# RefOsc10MHz_2V1.net
KiCad netlist of a schematic drawn in EAGLE
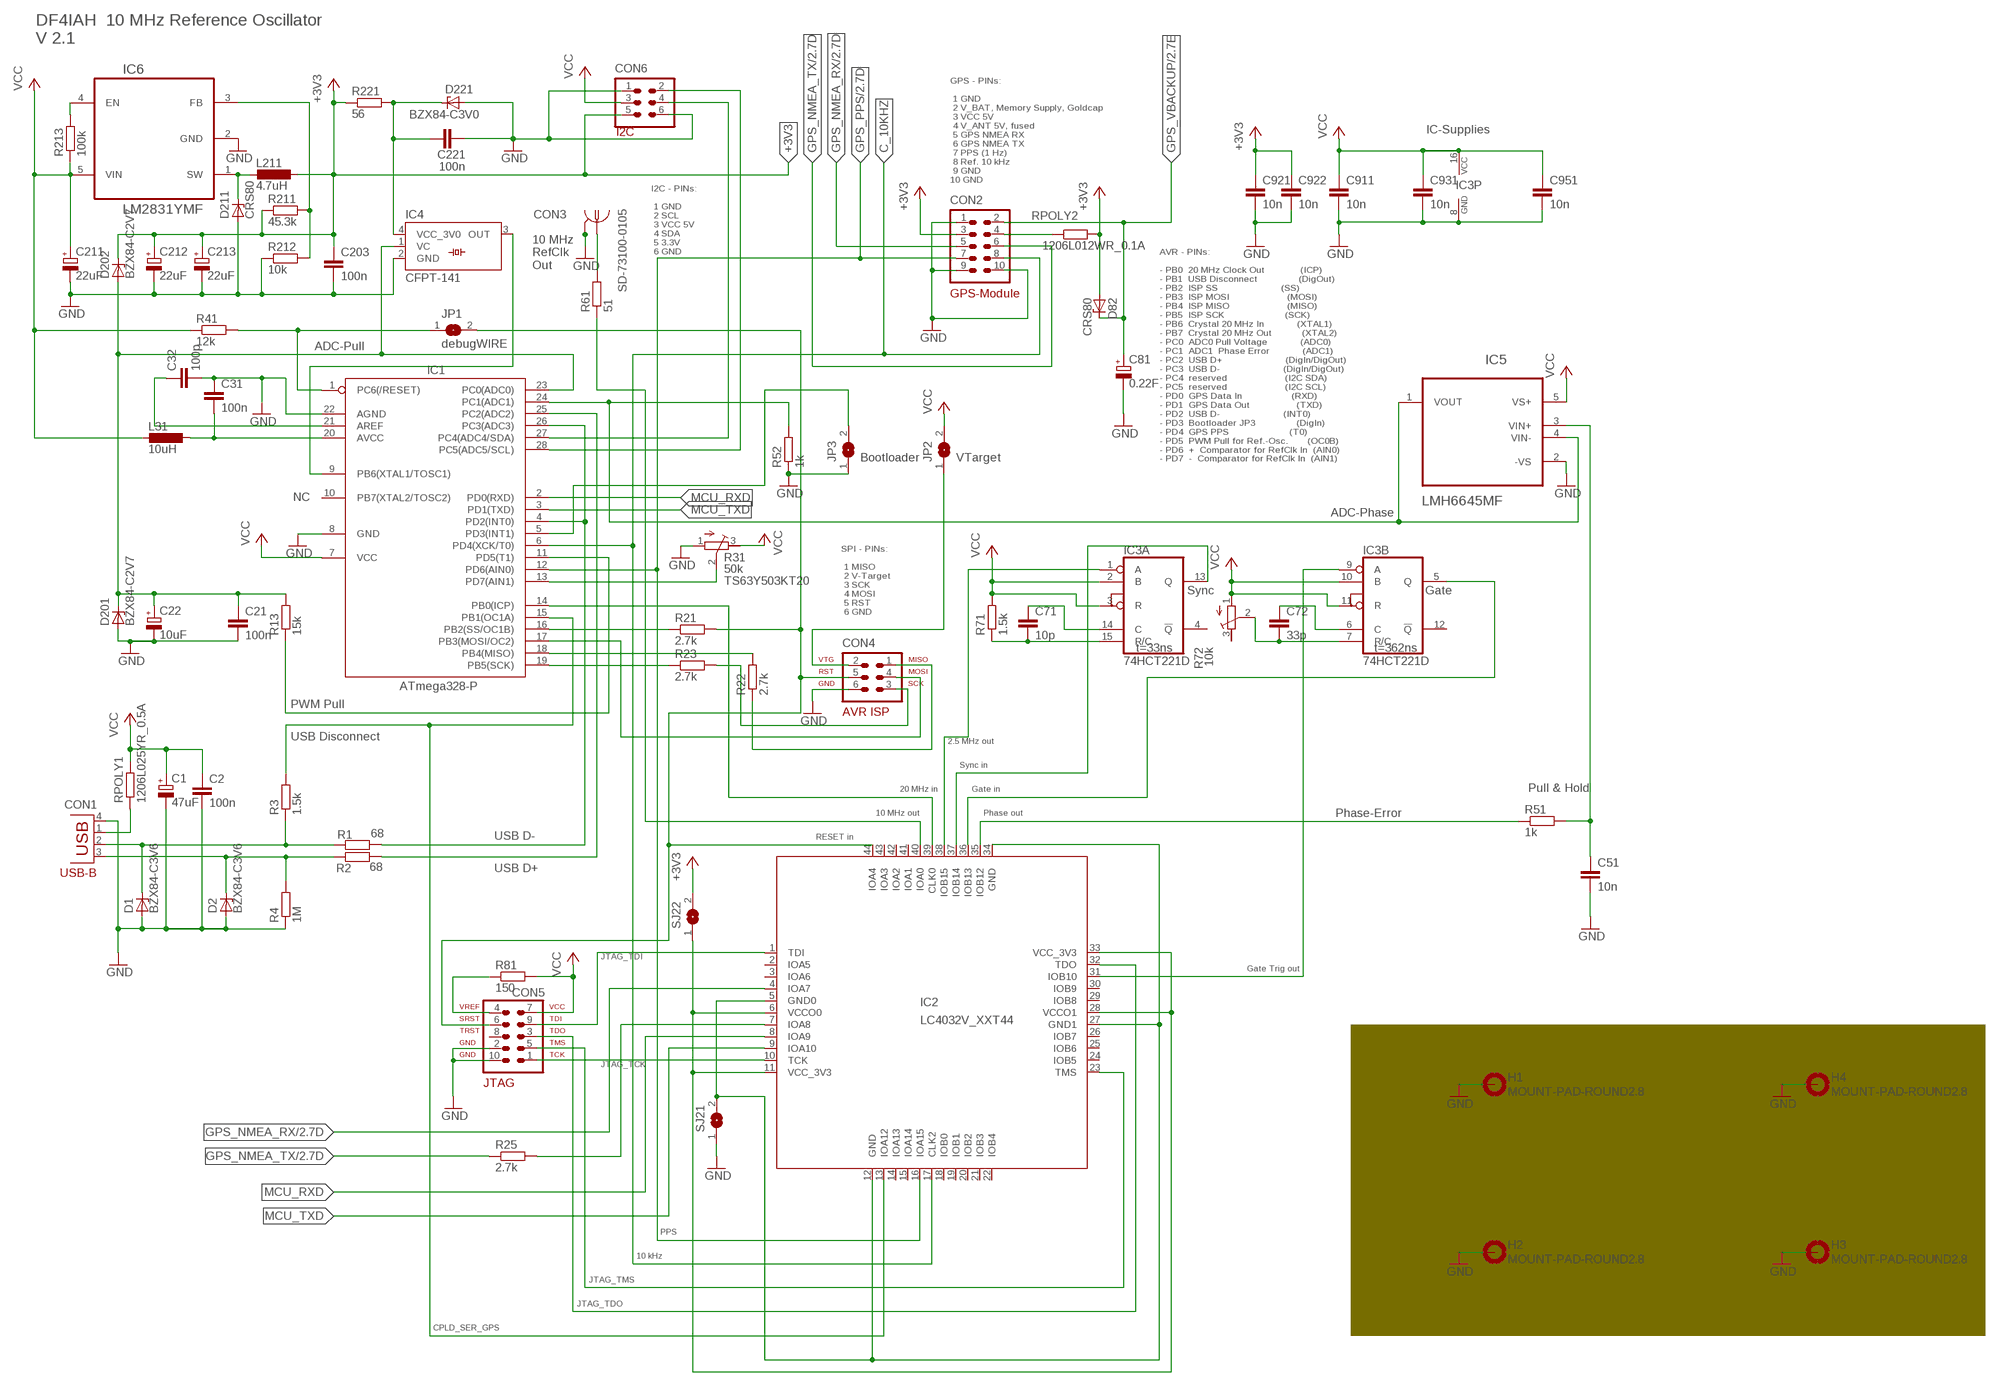
[diagram p0: schematic, sheet 1]
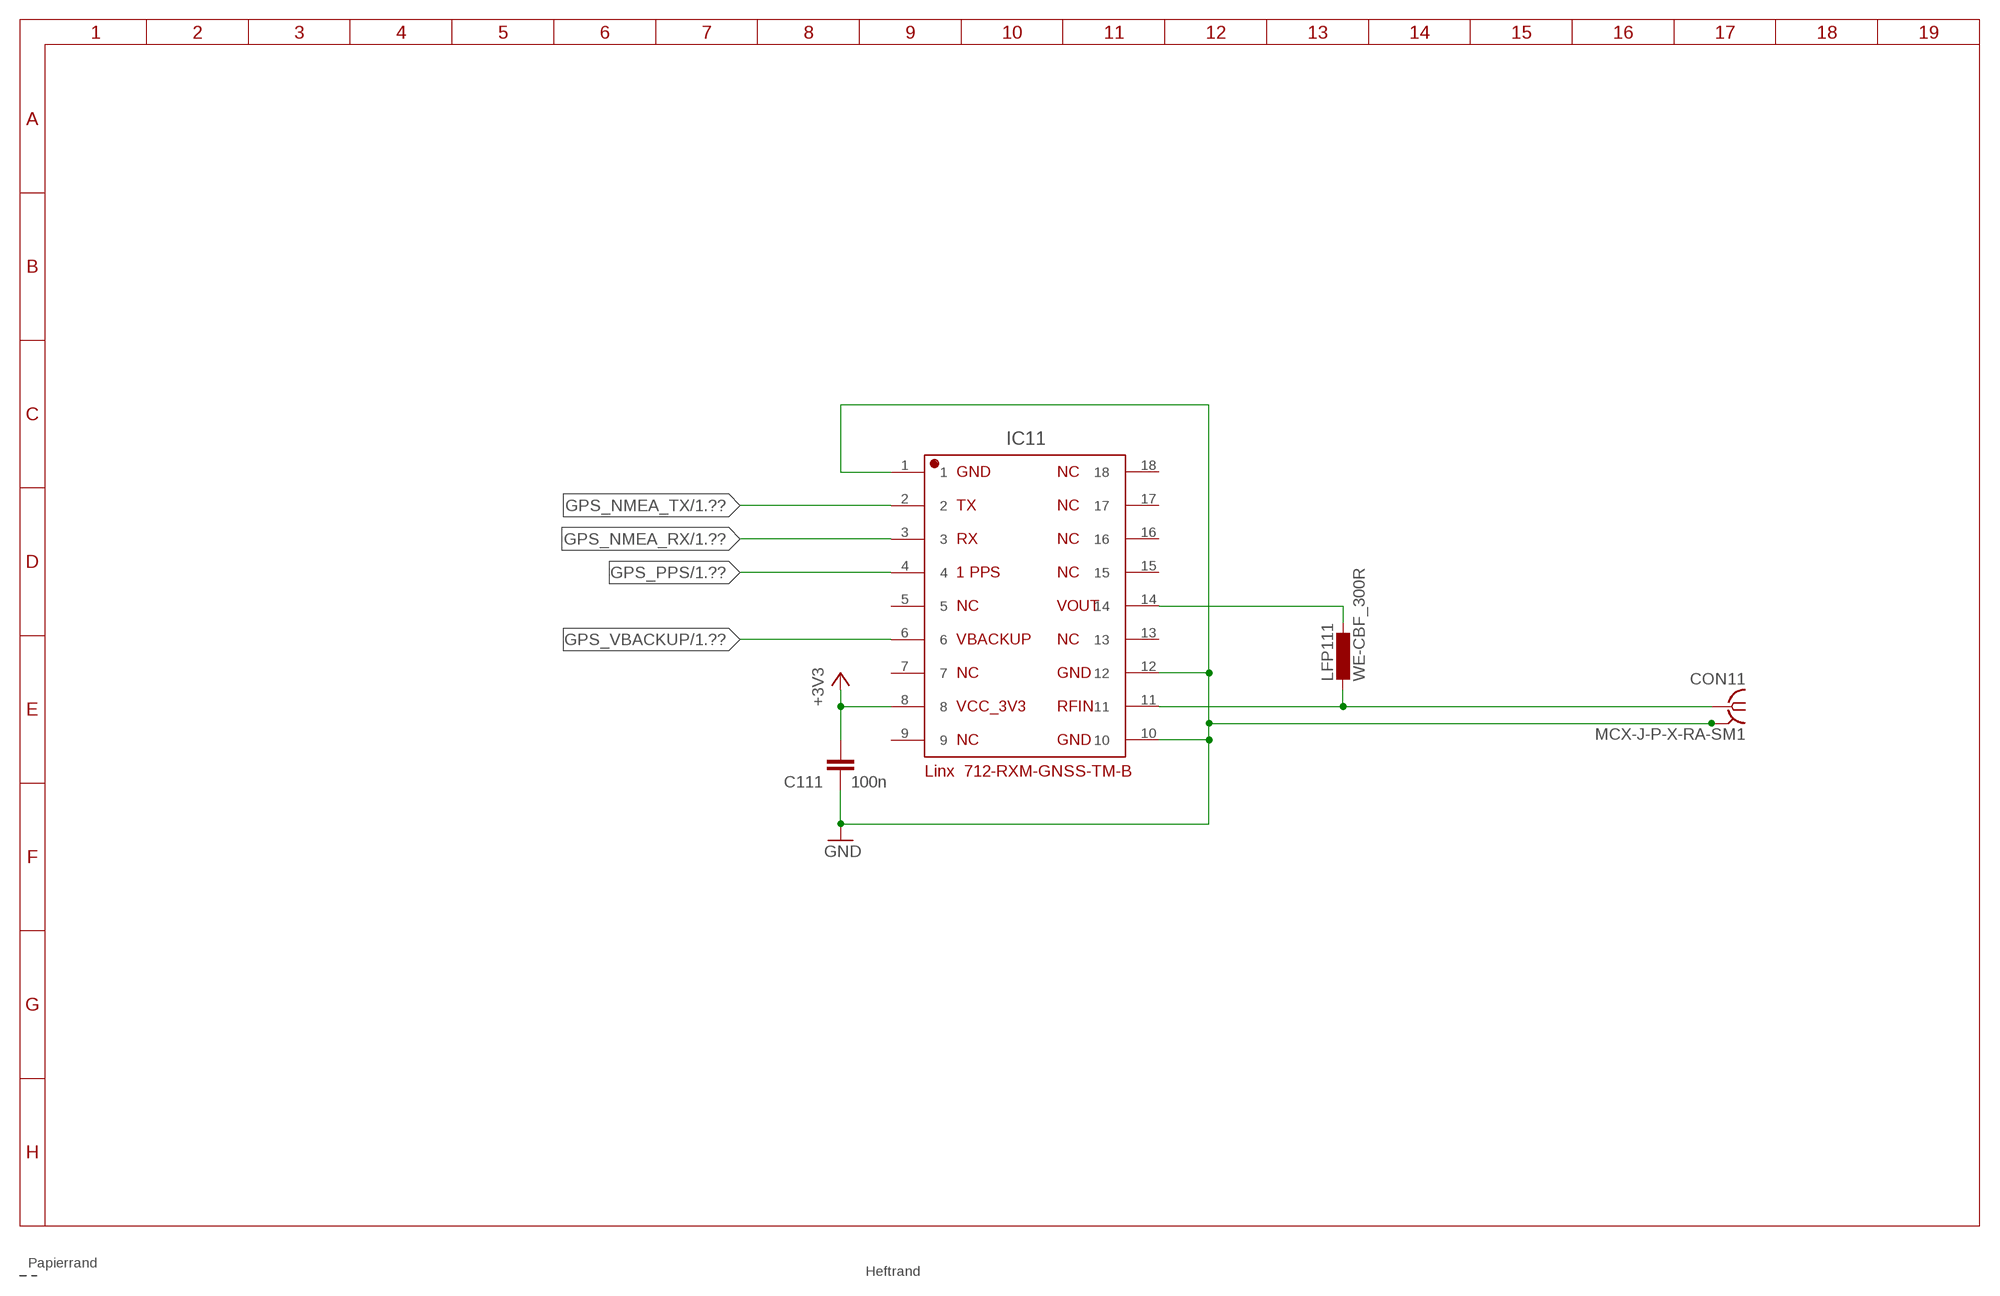
[diagram p1: schematic, sheet 2]

(export (version "E")
  (design (tool "Eeschema 10.0.6"))
  (components
    (comp (ref "C111")
      (value "100n")
      (footprint "eagle-import:C0805")
      (libsource (lib "eagle-import") (part "C-EUC0805"))
    )
    (comp (ref "CON11")
      (value "MCX-J-P-X-RA-SM1")
      (footprint "eagle-import:MCX-J-P-X-RA-SM1")
      (libsource (lib "eagle-import") (part "MCX-J-P-X-RA-SM1"))
    )
    (comp (ref "IC11")
      (value "712-RXM-GNSS-TM-B")
      (footprint "eagle-import:712-RXM-GNSS-TM-B")
      (libsource (lib "eagle-import") (part "712-RXM-GNSS-TM-B"))
    )
    (comp (ref "LFP111")
      (value "WE-CBF_300R")
      (footprint "eagle-import:L3216C")
      (libsource (lib "eagle-import") (part "L-EUL3216C"))
    )
    (comp (ref "C1")
      (value "47uF")
      (footprint "eagle-import:PANASONIC_C")
      (libsource (lib "eagle-import") (part "CPOL-EUC"))
    )
    (comp (ref "C2")
      (value "100n")
      (footprint "eagle-import:C0805")
      (libsource (lib "eagle-import") (part "rcl_C-EUC0805"))
    )
    (comp (ref "C21")
      (value "100n")
      (footprint "eagle-import:C0805")
      (libsource (lib "eagle-import") (part "rcl_C-EUC0805"))
    )
    (comp (ref "C22")
      (value "10uF")
      (footprint "eagle-import:PANASONIC_B")
      (libsource (lib "eagle-import") (part "CPOL-EUB"))
    )
    (comp (ref "C31")
      (value "100n")
      (footprint "eagle-import:C0805")
      (libsource (lib "eagle-import") (part "rcl_C-EUC0805"))
    )
    (comp (ref "C32")
      (value "100p")
      (footprint "eagle-import:C0805")
      (libsource (lib "eagle-import") (part "rcl_C-EUC0805"))
    )
    (comp (ref "C51")
      (value "10n")
      (footprint "eagle-import:C0805")
      (libsource (lib "eagle-import") (part "rcl_C-EUC0805"))
    )
    (comp (ref "C71")
      (value "10p")
      (footprint "eagle-import:C0805")
      (libsource (lib "eagle-import") (part "rcl_C-EUC0805"))
    )
    (comp (ref "C72")
      (value "33p")
      (footprint "eagle-import:C0805")
      (libsource (lib "eagle-import") (part "rcl_C-EUC0805"))
    )
    (comp (ref "C81")
      (value "0.22F")
      (footprint "eagle-import:140CLH-1010")
      (libsource (lib "eagle-import") (part "CPOL-EU140CLH-1010"))
    )
    (comp (ref "C203")
      (value "100n")
      (footprint "eagle-import:C0805")
      (libsource (lib "eagle-import") (part "rcl_C-EUC0805"))
    )
    (comp (ref "C211")
      (value "22uF")
      (footprint "eagle-import:A_3216-18W")
      (libsource (lib "eagle-import") (part "CPOL-EUA/3216-18W"))
    )
    (comp (ref "C212")
      (value "22uF")
      (footprint "eagle-import:A_3216-18W")
      (libsource (lib "eagle-import") (part "CPOL-EUA/3216-18W"))
    )
    (comp (ref "C213")
      (value "22uF")
      (footprint "eagle-import:A_3216-18W")
      (libsource (lib "eagle-import") (part "CPOL-EUA/3216-18W"))
    )
    (comp (ref "C221")
      (value "100n")
      (footprint "eagle-import:C0805")
      (libsource (lib "eagle-import") (part "rcl_C-EUC0805"))
    )
    (comp (ref "C911")
      (value "10n")
      (footprint "eagle-import:C0805")
      (libsource (lib "eagle-import") (part "rcl_C-EUC0805"))
    )
    (comp (ref "C921")
      (value "10n")
      (footprint "eagle-import:C0805")
      (libsource (lib "eagle-import") (part "rcl_C-EUC0805"))
    )
    (comp (ref "C922")
      (value "10n")
      (footprint "eagle-import:C0805")
      (libsource (lib "eagle-import") (part "rcl_C-EUC0805"))
    )
    (comp (ref "C931")
      (value "10n")
      (footprint "eagle-import:C0805")
      (libsource (lib "eagle-import") (part "rcl_C-EUC0805"))
    )
    (comp (ref "C951")
      (value "10n")
      (footprint "eagle-import:C0805")
      (libsource (lib "eagle-import") (part "rcl_C-EUC0805"))
    )
    (comp (ref "CON1")
      (value "TYCO-AMP_USBUSB-B_SMT")
      (footprint "eagle-import:TYCO-AMP_USB-B_SMT")
      (fields (field (name "MF") "TYCO-AMP") (field (name "MPN") "1734346"))
      (libsource (lib "eagle-import") (part "TYCO-AMP_USBUSB-B_SMT"))
    )
    (comp (ref "CON2")
      (value "HEADER-2X5SMD")
      (footprint "eagle-import:2X5SMD")
      (libsource (lib "eagle-import") (part "HEADER-2X5SMD"))
    )
    (comp (ref "CON3")
      (value "SD-73100-0105")
      (footprint "eagle-import:MOLEX_BNC-JACK-50R_SD-73100-0105")
      (fields (field (name "MF") "MOLEX"))
      (libsource (lib "eagle-import") (part "MOLEX_BNC-JACK-50R_SD-73100-0105"))
    )
    (comp (ref "CON4")
      (value "AVR-ISP-6SMD")
      (footprint "eagle-import:2X3SMD")
      (libsource (lib "eagle-import") (part "AVR-ISP-6SMD"))
    )
    (comp (ref "CON5")
      (value "AVR-JTAG-10SMD")
      (footprint "eagle-import:2X5SMD")
      (libsource (lib "eagle-import") (part "AVR-JTAG-10SMD"))
    )
    (comp (ref "CON6")
      (value "HEADER-2X3SMD")
      (footprint "eagle-import:2X03SMD")
      (libsource (lib "eagle-import") (part "HEADER-2X3SMD"))
    )
    (comp (ref "D1")
      (value "BZX84-C3V6")
      (footprint "eagle-import:TO236")
      (libsource (lib "eagle-import") (part "BZX84CSMD"))
    )
    (comp (ref "D2")
      (value "BZX84-C3V6")
      (footprint "eagle-import:TO236")
      (libsource (lib "eagle-import") (part "BZX84CSMD"))
    )
    (comp (ref "D82")
      (value "CRS80")
      (footprint "eagle-import:SOD80C")
      (libsource (lib "eagle-import") (part "ZENER-DIODESOD80C"))
    )
    (comp (ref "D201")
      (value "BZX84-C2V7")
      (footprint "eagle-import:TO236")
      (libsource (lib "eagle-import") (part "BZX84CSMD"))
    )
    (comp (ref "D202")
      (value "BZX84-C2V7")
      (footprint "eagle-import:TO236")
      (libsource (lib "eagle-import") (part "BZX84CSMD"))
    )
    (comp (ref "D211")
      (value "CRS80")
      (footprint "eagle-import:SOD80C")
      (libsource (lib "eagle-import") (part "ZENER-DIODESOD80C"))
    )
    (comp (ref "D221")
      (value "BZX84-C3V0")
      (footprint "eagle-import:TO236")
      (libsource (lib "eagle-import") (part "BZX84CSMD"))
    )
    (comp (ref "H1")
      (value "MOUNT-PAD-ROUND2.8")
      (footprint "eagle-import:2,8-PAD")
      (libsource (lib "eagle-import") (part "MOUNT-PAD-ROUND2.8"))
    )
    (comp (ref "H2")
      (value "MOUNT-PAD-ROUND2.8")
      (footprint "eagle-import:2,8-PAD")
      (libsource (lib "eagle-import") (part "MOUNT-PAD-ROUND2.8"))
    )
    (comp (ref "H3")
      (value "MOUNT-PAD-ROUND2.8")
      (footprint "eagle-import:2,8-PAD")
      (libsource (lib "eagle-import") (part "MOUNT-PAD-ROUND2.8"))
    )
    (comp (ref "H4")
      (value "MOUNT-PAD-ROUND2.8")
      (footprint "eagle-import:2,8-PAD")
      (libsource (lib "eagle-import") (part "MOUNT-PAD-ROUND2.8"))
    )
    (comp (ref "IC1")
      (value "ATmega328-P")
      (footprint "eagle-import:DIL28-3")
      (libsource (lib "eagle-import") (part "MEGA8-P"))
    )
    (comp (ref "IC2")
      (value "LC4032V_XXT44")
      (footprint "eagle-import:TQFP44")
      (libsource (lib "eagle-import") (part "LC4032V_XXT44"))
    )
    (comp (ref "IC3")
      (value "74HCT221D")
      (footprint "eagle-import:SO16")
      (libsource (lib "eagle-import") (part "74221DHCT"))
    )
    (comp (ref "IC4")
      (value "CFPT-141")
      (footprint "eagle-import:CFPT-141")
      (fields (field (name "MF") "IQD-FREQUENCY-PRODUCTS") (field (name "MPN") "LFTVXO022175"))
      (libsource (lib "eagle-import") (part "CFPT-141"))
    )
    (comp (ref "IC5")
      (value "LMH6645MF")
      (footprint "eagle-import:SOT95P280X145-5N")
      (libsource (lib "eagle-import") (part "LMH6645MF"))
    )
    (comp (ref "IC6")
      (value "LM2831YMF")
      (footprint "eagle-import:SOT95P280X145-5N")
      (fields (field (name "MPN") "LM2831YMF/NOPB"))
      (libsource (lib "eagle-import") (part "LM2831YMF"))
    )
    (comp (ref "JP1")
      (value "SJW")
      (footprint "eagle-import:SJW")
      (libsource (lib "eagle-import") (part "SJW"))
    )
    (comp (ref "JP2")
      (value "SJW")
      (footprint "eagle-import:SJW")
      (libsource (lib "eagle-import") (part "SJW"))
    )
    (comp (ref "JP3")
      (value "SJW")
      (footprint "eagle-import:SJW")
      (libsource (lib "eagle-import") (part "SJW"))
    )
    (comp (ref "L31")
      (value "10uH")
      (footprint "eagle-import:L1812")
      (libsource (lib "eagle-import") (part "rcl_L-EUL1812"))
    )
    (comp (ref "L211")
      (value "4.7uH")
      (footprint "eagle-import:L5650M")
      (libsource (lib "eagle-import") (part "rcl_L-EUL5650M"))
    )
    (comp (ref "R1")
      (value "68")
      (footprint "eagle-import:R0805")
      (libsource (lib "eagle-import") (part "R-EU_R0805"))
    )
    (comp (ref "R2")
      (value "68")
      (footprint "eagle-import:R0805")
      (libsource (lib "eagle-import") (part "R-EU_R0805"))
    )
    (comp (ref "R3")
      (value "1.5k")
      (footprint "eagle-import:R0805")
      (libsource (lib "eagle-import") (part "R-EU_R0805"))
    )
    (comp (ref "R4")
      (value "1M")
      (footprint "eagle-import:R0805")
      (libsource (lib "eagle-import") (part "R-EU_R0805"))
    )
    (comp (ref "R13")
      (value "15k")
      (footprint "eagle-import:R0805")
      (libsource (lib "eagle-import") (part "R-EU_R0805"))
    )
    (comp (ref "R21")
      (value "2.7k")
      (footprint "eagle-import:R0805")
      (libsource (lib "eagle-import") (part "R-EU_R0805"))
    )
    (comp (ref "R22")
      (value "2.7k")
      (footprint "eagle-import:R0805")
      (libsource (lib "eagle-import") (part "R-EU_R0805"))
    )
    (comp (ref "R23")
      (value "2.7k")
      (footprint "eagle-import:R0805")
      (libsource (lib "eagle-import") (part "R-EU_R0805"))
    )
    (comp (ref "R25")
      (value "2.7k")
      (footprint "eagle-import:R0805")
      (libsource (lib "eagle-import") (part "R-EU_R0805"))
    )
    (comp (ref "R31")
      (value "50k")
      (footprint "eagle-import:RTRIMTS63Y")
      (fields (field (name "NR") "TS63Y503KT20"))
      (libsource (lib "eagle-import") (part "R-TRIMMTS63Y"))
    )
    (comp (ref "R41")
      (value "12k")
      (footprint "eagle-import:R0805")
      (libsource (lib "eagle-import") (part "R-EU_R0805"))
    )
    (comp (ref "R51")
      (value "1k")
      (footprint "eagle-import:R0805")
      (libsource (lib "eagle-import") (part "R-EU_R0805"))
    )
    (comp (ref "R52")
      (value "1k")
      (footprint "eagle-import:R0805")
      (libsource (lib "eagle-import") (part "R-EU_R0805"))
    )
    (comp (ref "R61")
      (value "51")
      (footprint "eagle-import:R0805")
      (libsource (lib "eagle-import") (part "R-EU_R0805"))
    )
    (comp (ref "R71")
      (value "1.5k")
      (footprint "eagle-import:R0805")
      (libsource (lib "eagle-import") (part "R-EU_R0805"))
    )
    (comp (ref "R72")
      (value "10k")
      (footprint "eagle-import:RTRIMTS63Y")
      (libsource (lib "eagle-import") (part "R-TRIMMTS63Y"))
    )
    (comp (ref "R81")
      (value "150")
      (footprint "eagle-import:R0805")
      (libsource (lib "eagle-import") (part "R-EU_R0805"))
    )
    (comp (ref "R211")
      (value "45.3k")
      (footprint "eagle-import:R0805")
      (libsource (lib "eagle-import") (part "R-EU_R0805"))
    )
    (comp (ref "R212")
      (value "10k")
      (footprint "eagle-import:R0805")
      (libsource (lib "eagle-import") (part "R-EU_R0805"))
    )
    (comp (ref "R213")
      (value "100k")
      (footprint "eagle-import:R0805")
      (libsource (lib "eagle-import") (part "R-EU_R0805"))
    )
    (comp (ref "R221")
      (value "56")
      (footprint "eagle-import:R0805")
      (libsource (lib "eagle-import") (part "R-EU_R0805"))
    )
    (comp (ref "RPOLY1")
      (value "1206L025YR_0.5A")
      (footprint "eagle-import:M1206")
      (libsource (lib "eagle-import") (part "R-EU_M1206"))
    )
    (comp (ref "RPOLY2")
      (value "1206L012WR_0.1A")
      (footprint "eagle-import:M1206")
      (libsource (lib "eagle-import") (part "R-EU_M1206"))
    )
    (comp (ref "SJ21")
      (value "SJ")
      (footprint "eagle-import:SJ")
      (libsource (lib "eagle-import") (part "SJ"))
    )
    (comp (ref "SJ22")
      (value "SJ")
      (footprint "eagle-import:SJ")
      (libsource (lib "eagle-import") (part "SJ"))
    )
  )
  (nets
    (net (code "1") (name "+3V3") (class "Default")
      (node (ref "C111") (pin "1") (pinfunction "1_1") (pintype "passive"))
      (node (ref "C203") (pin "1") (pinfunction "1_1") (pintype "passive"))
      (node (ref "C212") (pin "+") (pinfunction "+_+") (pintype "passive"))
      (node (ref "C213") (pin "+") (pinfunction "+_+") (pintype "passive"))
      (node (ref "C921") (pin "1") (pinfunction "1_1") (pintype "passive"))
      (node (ref "C922") (pin "1") (pinfunction "1_1") (pintype "passive"))
      (node (ref "CON2") (pin "3") (pinfunction "3_3") (pintype "passive"))
      (node (ref "CON6") (pin "5") (pinfunction "5_5") (pintype "passive"))
      (node (ref "D202") (pin "C") (pinfunction "C_C") (pintype "passive"))
      (node (ref "D82") (pin "A") (pinfunction "A_A") (pintype "passive"))
      (node (ref "IC11") (pin "8") (pinfunction "8_8") (pintype "power_in"))
      (node (ref "L211") (pin "1") (pinfunction "1_1") (pintype "passive"))
      (node (ref "R211") (pin "1") (pinfunction "1_1") (pintype "passive"))
      (node (ref "R221") (pin "1") (pinfunction "1_1") (pintype "passive"))
      (node (ref "RPOLY2") (pin "2") (pinfunction "2_2") (pintype "passive"))
      (node (ref "SJ22") (pin "2") (pinfunction "2_2") (pintype "passive"))
    )
    (net (code "2") (name "C_10KHZ") (class "Default")
      (node (ref "CON2") (pin "8") (pinfunction "8_8") (pintype "passive"))
      (node (ref "IC1") (pin "6") (pinfunction "PD4(XCK/T0)_6") (pintype "bidirectional"))
      (node (ref "IC2") (pin "17") (pinfunction "CLK2_17") (pintype "input"))
    )
    (net (code "3") (name "GND") (class "Default")
      (node (ref "C1") (pin "-") (pinfunction "-_-") (pintype "passive"))
      (node (ref "C111") (pin "2") (pinfunction "2_2") (pintype "passive"))
      (node (ref "C2") (pin "2") (pinfunction "2_2") (pintype "passive"))
      (node (ref "C203") (pin "2") (pinfunction "2_2") (pintype "passive"))
      (node (ref "C21") (pin "2") (pinfunction "2_2") (pintype "passive"))
      (node (ref "C211") (pin "-") (pinfunction "-_-") (pintype "passive"))
      (node (ref "C212") (pin "-") (pinfunction "-_-") (pintype "passive"))
      (node (ref "C213") (pin "-") (pinfunction "-_-") (pintype "passive"))
      (node (ref "C22") (pin "-") (pinfunction "-_-") (pintype "passive"))
      (node (ref "C221") (pin "2") (pinfunction "2_2") (pintype "passive"))
      (node (ref "C31") (pin "1") (pinfunction "1_1") (pintype "passive"))
      (node (ref "C32") (pin "2") (pinfunction "2_2") (pintype "passive"))
      (node (ref "C51") (pin "2") (pinfunction "2_2") (pintype "passive"))
      (node (ref "C81") (pin "-") (pinfunction "-_-") (pintype "passive"))
      (node (ref "C911") (pin "2") (pinfunction "2_2") (pintype "passive"))
      (node (ref "C921") (pin "2") (pinfunction "2_2") (pintype "passive"))
      (node (ref "C922") (pin "2") (pinfunction "2_2") (pintype "passive"))
      (node (ref "C931") (pin "2") (pinfunction "2_2") (pintype "passive"))
      (node (ref "C951") (pin "2") (pinfunction "2_2") (pintype "passive"))
      (node (ref "CON1") (pin "4") (pinfunction "GND_4") (pintype "bidirectional"))
      (node (ref "CON11") (pin "2") (pinfunction "2_2") (pintype "passive"))
      (node (ref "CON11") (pin "3") (pinfunction "3_3") (pintype "passive"))
      (node (ref "CON11") (pin "4") (pinfunction "4_4") (pintype "passive"))
      (node (ref "CON11") (pin "5") (pinfunction "5_5") (pintype "passive"))
      (node (ref "CON2") (pin "1") (pinfunction "1_1") (pintype "passive"))
      (node (ref "CON2") (pin "10") (pinfunction "10_10") (pintype "passive"))
      (node (ref "CON2") (pin "9") (pinfunction "9_9") (pintype "passive"))
      (node (ref "CON3") (pin "2") (pinfunction "2_2") (pintype "passive"))
      (node (ref "CON3") (pin "3") (pinfunction "3_3") (pintype "passive"))
      (node (ref "CON4") (pin "6") (pinfunction "6_6") (pintype "passive"))
      (node (ref "CON5") (pin "10") (pinfunction "10_10") (pintype "passive"))
      (node (ref "CON5") (pin "2") (pinfunction "2_2") (pintype "passive"))
      (node (ref "CON6") (pin "1") (pinfunction "1_1") (pintype "passive"))
      (node (ref "CON6") (pin "6") (pinfunction "6_6") (pintype "passive"))
      (node (ref "D1") (pin "A") (pinfunction "A_A") (pintype "passive"))
      (node (ref "D2") (pin "A") (pinfunction "A_A") (pintype "passive"))
      (node (ref "D201") (pin "A") (pinfunction "A_A") (pintype "passive"))
      (node (ref "D211") (pin "A") (pinfunction "A_A") (pintype "passive"))
      (node (ref "D221") (pin "A") (pinfunction "A_A") (pintype "passive"))
      (node (ref "H1") (pin "B2,8") (pinfunction "MOUNT_B2,8") (pintype "passive"))
      (node (ref "H2") (pin "B2,8") (pinfunction "MOUNT_B2,8") (pintype "passive"))
      (node (ref "H3") (pin "B2,8") (pinfunction "MOUNT_B2,8") (pintype "passive"))
      (node (ref "H4") (pin "B2,8") (pinfunction "MOUNT_B2,8") (pintype "passive"))
      (node (ref "IC1") (pin "22") (pinfunction "AGND_22") (pintype "bidirectional"))
      (node (ref "IC1") (pin "8") (pinfunction "GND_8") (pintype "bidirectional"))
      (node (ref "IC11") (pin "1") (pinfunction "1_1") (pintype "power_in"))
      (node (ref "IC11") (pin "10") (pinfunction "10_10") (pintype "power_in"))
      (node (ref "IC11") (pin "12") (pinfunction "12_12") (pintype "power_in"))
      (node (ref "IC3") (pin "8") (pinfunction "GND_8") (pintype "power_in"))
      (node (ref "IC4") (pin "2") (pinfunction "GND_2") (pintype "power_in"))
      (node (ref "IC5") (pin "2") (pinfunction "-VS_2") (pintype "power_in"))
      (node (ref "IC6") (pin "2") (pinfunction "GND_2") (pintype "passive"))
      (node (ref "JP3") (pin "1") (pinfunction "1_1") (pintype "passive"))
      (node (ref "R212") (pin "1") (pinfunction "1_1") (pintype "passive"))
      (node (ref "R31") (pin "1") (pinfunction "A_1") (pintype "passive"))
      (node (ref "R4") (pin "1") (pinfunction "1_1") (pintype "passive"))
      (node (ref "R52") (pin "1") (pinfunction "1_1") (pintype "passive"))
      (node (ref "SJ21") (pin "1") (pinfunction "1_1") (pintype "passive"))
    )
    (net (code "4") (name "GPS_NMEA_RX") (class "Default")
      (node (ref "CON2") (pin "5") (pinfunction "5_5") (pintype "passive"))
      (node (ref "IC11") (pin "3") (pinfunction "3_3") (pintype "output"))
      (node (ref "IC2") (pin "4") (pinfunction "IOA7_4") (pintype "bidirectional"))
    )
    (net (code "5") (name "GPS_NMEA_TX") (class "Default")
      (node (ref "CON2") (pin "6") (pinfunction "6_6") (pintype "passive"))
      (node (ref "IC11") (pin "2") (pinfunction "2_2") (pintype "input"))
      (node (ref "R25") (pin "1") (pinfunction "1_1") (pintype "passive"))
    )
    (net (code "6") (name "GPS_PPS") (class "Default")
      (node (ref "CON2") (pin "7") (pinfunction "7_7") (pintype "passive"))
      (node (ref "IC1") (pin "12") (pinfunction "PD6(AIN0)_12") (pintype "bidirectional"))
      (node (ref "IC11") (pin "4") (pinfunction "4_4") (pintype "output"))
      (node (ref "IC2") (pin "16") (pinfunction "IOA15_16") (pintype "bidirectional"))
    )
    (net (code "7") (name "GPS_VBACKUP") (class "Default")
      (node (ref "C81") (pin "+") (pinfunction "+_+") (pintype "passive"))
      (node (ref "CON2") (pin "2") (pinfunction "2_2") (pintype "passive"))
      (node (ref "D82") (pin "C") (pinfunction "C_C") (pintype "passive"))
      (node (ref "IC11") (pin "6") (pinfunction "6_6") (pintype "power_in"))
    )
    (net (code "8") (name "MCU_RXD") (class "Default")
      (node (ref "IC1") (pin "2") (pinfunction "PD0(RXD)_2") (pintype "bidirectional"))
      (node (ref "IC2") (pin "8") (pinfunction "IOA9_8") (pintype "bidirectional"))
    )
    (net (code "9") (name "MCU_TXD") (class "Default")
      (node (ref "IC1") (pin "3") (pinfunction "PD1(TXD)_3") (pintype "bidirectional"))
      (node (ref "IC2") (pin "9") (pinfunction "IOA10_9") (pintype "bidirectional"))
    )
    (net (code "10") (name "Net-(CON1-D+)") (class "Default")
      (node (ref "CON1") (pin "3") (pinfunction "D+_3") (pintype "bidirectional"))
      (node (ref "D2") (pin "C") (pinfunction "C_C") (pintype "passive"))
      (node (ref "R2") (pin "1") (pinfunction "1_1") (pintype "passive"))
      (node (ref "R4") (pin "2") (pinfunction "2_2") (pintype "passive"))
    )
    (net (code "11") (name "Net-(CON1-D-)") (class "Default")
      (node (ref "CON1") (pin "2") (pinfunction "D-_2") (pintype "bidirectional"))
      (node (ref "D1") (pin "C") (pinfunction "C_C") (pintype "passive"))
      (node (ref "R1") (pin "1") (pinfunction "1_1") (pintype "passive"))
      (node (ref "R3") (pin "1") (pinfunction "1_1") (pintype "passive"))
    )
    (net (code "12") (name "Net-(CON1-VBUS)") (class "Default")
      (node (ref "CON1") (pin "1") (pinfunction "VBUS_1") (pintype "bidirectional"))
      (node (ref "RPOLY1") (pin "1") (pinfunction "1_1") (pintype "passive"))
    )
    (net (code "13") (name "Net-(CON2-Pad4)") (class "Default")
      (node (ref "CON2") (pin "4") (pinfunction "4_4") (pintype "passive"))
      (node (ref "RPOLY2") (pin "1") (pinfunction "1_1") (pintype "passive"))
    )
    (net (code "14") (name "Net-(CON3-Pad1)") (class "Default")
      (node (ref "CON3") (pin "1") (pinfunction "1_1") (pintype "passive"))
      (node (ref "R61") (pin "2") (pinfunction "2_2") (pintype "passive"))
    )
    (net (code "15") (name "Net-(CON4-Pad1)") (class "Default")
      (node (ref "CON4") (pin "1") (pinfunction "1_1") (pintype "passive"))
      (node (ref "R22") (pin "1") (pinfunction "1_1") (pintype "passive"))
    )
    (net (code "16") (name "Net-(CON4-Pad2)") (class "Default")
      (node (ref "CON4") (pin "2") (pinfunction "2_2") (pintype "passive"))
      (node (ref "JP2") (pin "1") (pinfunction "1_1") (pintype "passive"))
    )
    (net (code "17") (name "Net-(CON4-Pad3)") (class "Default")
      (node (ref "CON4") (pin "3") (pinfunction "3_3") (pintype "passive"))
      (node (ref "R23") (pin "2") (pinfunction "2_2") (pintype "passive"))
    )
    (net (code "18") (name "Net-(CON5-Pad4)") (class "Default")
      (node (ref "CON5") (pin "4") (pinfunction "4_4") (pintype "passive"))
      (node (ref "R81") (pin "1") (pinfunction "1_1") (pintype "passive"))
    )
    (net (code "19") (name "Net-(CON11-Pad1)") (class "Default")
      (node (ref "CON11") (pin "1") (pinfunction "1_1") (pintype "passive"))
      (node (ref "IC11") (pin "11") (pinfunction "11_11") (pintype "input"))
      (node (ref "LFP111") (pin "2") (pinfunction "2_2") (pintype "passive"))
    )
    (net (code "20") (name "Net-(IC1-AREF)") (class "Default")
      (node (ref "C32") (pin "1") (pinfunction "1_1") (pintype "passive"))
      (node (ref "IC1") (pin "21") (pinfunction "AREF_21") (pintype "bidirectional"))
    )
    (net (code "21") (name "Net-(IC1-AVCC)") (class "Default")
      (node (ref "C31") (pin "2") (pinfunction "2_2") (pintype "passive"))
      (node (ref "IC1") (pin "20") (pinfunction "AVCC_20") (pintype "bidirectional"))
      (node (ref "L31") (pin "1") (pinfunction "1_1") (pintype "passive"))
    )
    (net (code "22") (name "Net-(IC1-PB0(ICP))") (class "Default")
      (node (ref "IC1") (pin "14") (pinfunction "PB0(ICP)_14") (pintype "bidirectional"))
      (node (ref "IC2") (pin "39") (pinfunction "CLK0_39") (pintype "input"))
    )
    (net (code "23") (name "Net-(IC1-PB1(OC1A))") (class "Default")
      (node (ref "IC1") (pin "15") (pinfunction "PB1(OC1A)_15") (pintype "bidirectional"))
      (node (ref "IC2") (pin "13") (pinfunction "IOA12_13") (pintype "bidirectional"))
      (node (ref "R3") (pin "2") (pinfunction "2_2") (pintype "passive"))
    )
    (net (code "24") (name "Net-(IC1-PB2(SS{slash}OC1B))") (class "Default")
      (node (ref "IC1") (pin "16") (pinfunction "PB2(SS/OC1B)_16") (pintype "bidirectional"))
      (node (ref "R21") (pin "1") (pinfunction "1_1") (pintype "passive"))
    )
    (net (code "25") (name "Net-(IC1-PB3(MOSI{slash}OC2))") (class "Default")
      (node (ref "CON4") (pin "4") (pinfunction "4_4") (pintype "passive"))
      (node (ref "IC1") (pin "17") (pinfunction "PB3(MOSI/OC2)_17") (pintype "bidirectional"))
    )
    (net (code "26") (name "Net-(IC1-PB4(MISO))") (class "Default")
      (node (ref "IC1") (pin "18") (pinfunction "PB4(MISO)_18") (pintype "bidirectional"))
      (node (ref "R22") (pin "2") (pinfunction "2_2") (pintype "passive"))
    )
    (net (code "27") (name "Net-(IC1-PB5(SCK))") (class "Default")
      (node (ref "IC1") (pin "19") (pinfunction "PB5(SCK)_19") (pintype "bidirectional"))
      (node (ref "R23") (pin "1") (pinfunction "1_1") (pintype "passive"))
    )
    (net (code "28") (name "Net-(IC1-PB6(XTAL1{slash}TOSC1))") (class "Default")
      (node (ref "IC1") (pin "9") (pinfunction "PB6(XTAL1/TOSC1)_9") (pintype "bidirectional"))
      (node (ref "IC4") (pin "3") (pinfunction "OUT_3") (pintype "output"))
    )
    (net (code "29") (name "Net-(IC1-PC0(ADC0))") (class "Default")
      (node (ref "C21") (pin "1") (pinfunction "1_1") (pintype "passive"))
      (node (ref "C22") (pin "+") (pinfunction "+_+") (pintype "passive"))
      (node (ref "D201") (pin "C") (pinfunction "C_C") (pintype "passive"))
      (node (ref "D202") (pin "A") (pinfunction "A_A") (pintype "passive"))
      (node (ref "IC1") (pin "23") (pinfunction "PC0(ADC0)_23") (pintype "bidirectional"))
      (node (ref "IC4") (pin "1") (pinfunction "VC_1") (pintype "input"))
      (node (ref "R13") (pin "2") (pinfunction "2_2") (pintype "passive"))
    )
    (net (code "30") (name "Net-(IC1-PC1(ADC1))") (class "Default")
      (node (ref "IC1") (pin "24") (pinfunction "PC1(ADC1)_24") (pintype "bidirectional"))
      (node (ref "IC5") (pin "1") (pinfunction "VOUT_1") (pintype "output"))
      (node (ref "IC5") (pin "4") (pinfunction "VIN-_4") (pintype "input"))
      (node (ref "R52") (pin "2") (pinfunction "2_2") (pintype "passive"))
    )
    (net (code "31") (name "Net-(IC1-PC2(ADC2))") (class "Default")
      (node (ref "IC1") (pin "25") (pinfunction "PC2(ADC2)_25") (pintype "bidirectional"))
      (node (ref "R2") (pin "2") (pinfunction "2_2") (pintype "passive"))
    )
    (net (code "32") (name "Net-(IC1-PC3(ADC3))") (class "Default")
      (node (ref "IC1") (pin "26") (pinfunction "PC3(ADC3)_26") (pintype "bidirectional"))
      (node (ref "IC1") (pin "4") (pinfunction "PD2(INT0)_4") (pintype "bidirectional"))
      (node (ref "R1") (pin "2") (pinfunction "2_2") (pintype "passive"))
    )
    (net (code "33") (name "Net-(IC1-PC4(ADC4{slash}SDA))") (class "Default")
      (node (ref "CON6") (pin "4") (pinfunction "4_4") (pintype "passive"))
      (node (ref "IC1") (pin "27") (pinfunction "PC4(ADC4/SDA)_27") (pintype "bidirectional"))
    )
    (net (code "34") (name "Net-(IC1-PC5(ADC5{slash}SCL))") (class "Default")
      (node (ref "CON6") (pin "2") (pinfunction "2_2") (pintype "passive"))
      (node (ref "IC1") (pin "28") (pinfunction "PC5(ADC5/SCL)_28") (pintype "bidirectional"))
    )
    (net (code "35") (name "Net-(IC1-PC6({slash}RESET))") (class "Default")
      (node (ref "IC1") (pin "1") (pinfunction "PC6(/RESET)_1") (pintype "bidirectional"))
      (node (ref "JP1") (pin "1") (pinfunction "1_1") (pintype "passive"))
      (node (ref "R41") (pin "2") (pinfunction "2_2") (pintype "passive"))
    )
    (net (code "36") (name "Net-(IC1-PD3(INT1))") (class "Default")
      (node (ref "IC1") (pin "5") (pinfunction "PD3(INT1)_5") (pintype "bidirectional"))
      (node (ref "JP3") (pin "2") (pinfunction "2_2") (pintype "passive"))
    )
    (net (code "37") (name "Net-(IC1-PD5(T1))") (class "Default")
      (node (ref "IC1") (pin "11") (pinfunction "PD5(T1)_11") (pintype "bidirectional"))
      (node (ref "R13") (pin "1") (pinfunction "1_1") (pintype "passive"))
    )
    (net (code "38") (name "Net-(IC1-PD7(AIN1))") (class "Default")
      (node (ref "IC1") (pin "13") (pinfunction "PD7(AIN1)_13") (pintype "bidirectional"))
      (node (ref "R31") (pin "2") (pinfunction "S_2") (pintype "passive"))
    )
    (net (code "39") (name "Net-(IC2-GND0)") (class "Default")
      (node (ref "IC2") (pin "12") (pinfunction "GND_12") (pintype "power_in"))
      (node (ref "IC2") (pin "27") (pinfunction "GND1_27") (pintype "power_in"))
      (node (ref "IC2") (pin "34") (pinfunction "GND_34") (pintype "power_in"))
      (node (ref "IC2") (pin "5") (pinfunction "GND0_5") (pintype "power_in"))
      (node (ref "SJ21") (pin "2") (pinfunction "2_2") (pintype "passive"))
    )
    (net (code "40") (name "Net-(IC2-IOA0)") (class "Default")
      (node (ref "IC2") (pin "40") (pinfunction "IOA0_40") (pintype "bidirectional"))
      (node (ref "R61") (pin "1") (pinfunction "1_1") (pintype "passive"))
    )
    (net (code "41") (name "Net-(IC2-IOA4)") (class "Default")
      (node (ref "CON4") (pin "5") (pinfunction "5_5") (pintype "passive"))
      (node (ref "CON5") (pin "6") (pinfunction "6_6") (pintype "passive"))
      (node (ref "IC2") (pin "44") (pinfunction "IOA4_44") (pintype "bidirectional"))
      (node (ref "JP1") (pin "2") (pinfunction "2_2") (pintype "passive"))
      (node (ref "R21") (pin "2") (pinfunction "2_2") (pintype "passive"))
    )
    (net (code "42") (name "Net-(IC2-IOA8)") (class "Default")
      (node (ref "IC2") (pin "7") (pinfunction "IOA8_7") (pintype "bidirectional"))
      (node (ref "R25") (pin "2") (pinfunction "2_2") (pintype "passive"))
    )
    (net (code "43") (name "Net-(IC2-IOB10)") (class "Default")
      (node (ref "IC2") (pin "31") (pinfunction "IOB10_31") (pintype "bidirectional"))
      (node (ref "IC3") (pin "9") (pinfunction "A_9") (pintype "input"))
    )
    (net (code "44") (name "Net-(IC2-IOB12)") (class "Default")
      (node (ref "IC2") (pin "35") (pinfunction "IOB12_35") (pintype "bidirectional"))
      (node (ref "R51") (pin "1") (pinfunction "1_1") (pintype "passive"))
    )
    (net (code "45") (name "Net-(IC2-IOB13)") (class "Default")
      (node (ref "IC2") (pin "36") (pinfunction "IOB13_36") (pintype "bidirectional"))
      (node (ref "IC3") (pin "5") (pinfunction "Q_5") (pintype "output"))
    )
    (net (code "46") (name "Net-(IC2-IOB14)") (class "Default")
      (node (ref "IC2") (pin "37") (pinfunction "IOB14_37") (pintype "bidirectional"))
      (node (ref "IC3") (pin "13") (pinfunction "Q_13") (pintype "output"))
    )
    (net (code "47") (name "Net-(IC2-IOB15)") (class "Default")
      (node (ref "IC2") (pin "38") (pinfunction "IOB15_38") (pintype "bidirectional"))
      (node (ref "IC3") (pin "1") (pinfunction "A_1") (pintype "input"))
    )
    (net (code "48") (name "Net-(IC2-TCK)") (class "Default")
      (node (ref "CON5") (pin "1") (pinfunction "1_1") (pintype "passive"))
      (node (ref "IC2") (pin "10") (pinfunction "TCK_10") (pintype "input"))
    )
    (net (code "49") (name "Net-(IC2-TDI)") (class "Default")
      (node (ref "CON5") (pin "9") (pinfunction "9_9") (pintype "passive"))
      (node (ref "IC2") (pin "1") (pinfunction "TDI_1") (pintype "input"))
    )
    (net (code "50") (name "Net-(IC2-TDO)") (class "Default")
      (node (ref "CON5") (pin "3") (pinfunction "3_3") (pintype "passive"))
      (node (ref "IC2") (pin "32") (pinfunction "TDO_32") (pintype "output"))
    )
    (net (code "51") (name "Net-(IC2-TMS)") (class "Default")
      (node (ref "CON5") (pin "5") (pinfunction "5_5") (pintype "passive"))
      (node (ref "IC2") (pin "23") (pinfunction "TMS_23") (pintype "input"))
    )
    (net (code "52") (name "Net-(IC2-VCCO0)") (class "Default")
      (node (ref "IC2") (pin "11") (pinfunction "VCC_3V3_11") (pintype "power_in"))
      (node (ref "IC2") (pin "28") (pinfunction "VCCO1_28") (pintype "power_in"))
      (node (ref "IC2") (pin "33") (pinfunction "VCC_3V3_33") (pintype "power_in"))
      (node (ref "IC2") (pin "6") (pinfunction "VCCO0_6") (pintype "power_in"))
      (node (ref "SJ22") (pin "1") (pinfunction "1_1") (pintype "passive"))
    )
    (net (code "53") (name "Net-(IC3A-C)") (class "Default")
      (node (ref "C71") (pin "1") (pinfunction "1_1") (pintype "passive"))
      (node (ref "IC3") (pin "14") (pinfunction "C_14") (pintype "input"))
    )
    (net (code "54") (name "Net-(IC3A-R{slash}C)") (class "Default")
      (node (ref "C71") (pin "2") (pinfunction "2_2") (pintype "passive"))
      (node (ref "IC3") (pin "15") (pinfunction "R/C_15") (pintype "input"))
      (node (ref "R71") (pin "1") (pinfunction "1_1") (pintype "passive"))
    )
    (net (code "55") (name "Net-(IC3B-C)") (class "Default")
      (node (ref "C72") (pin "1") (pinfunction "1_1") (pintype "passive"))
      (node (ref "IC3") (pin "6") (pinfunction "C_6") (pintype "input"))
    )
    (net (code "56") (name "Net-(IC3B-R{slash}C)") (class "Default")
      (node (ref "C72") (pin "2") (pinfunction "2_2") (pintype "passive"))
      (node (ref "IC3") (pin "7") (pinfunction "R/C_7") (pintype "input"))
      (node (ref "R72") (pin "2") (pinfunction "S_2") (pintype "passive"))
    )
    (net (code "57") (name "Net-(IC4-VCC_3V0)") (class "Default")
      (node (ref "C221") (pin "1") (pinfunction "1_1") (pintype "passive"))
      (node (ref "D221") (pin "C") (pinfunction "C_C") (pintype "passive"))
      (node (ref "IC4") (pin "4") (pinfunction "VCC_3V0_4") (pintype "power_in"))
      (node (ref "R221") (pin "2") (pinfunction "2_2") (pintype "passive"))
    )
    (net (code "58") (name "Net-(IC5-VIN+)") (class "Default")
      (node (ref "C51") (pin "1") (pinfunction "1_1") (pintype "passive"))
      (node (ref "IC5") (pin "3") (pinfunction "VIN+_3") (pintype "input"))
      (node (ref "R51") (pin "2") (pinfunction "2_2") (pintype "passive"))
    )
    (net (code "59") (name "Net-(IC6-EN)") (class "Default")
      (node (ref "IC6") (pin "4") (pinfunction "EN_4") (pintype "input"))
      (node (ref "R213") (pin "2") (pinfunction "2_2") (pintype "passive"))
    )
    (net (code "60") (name "Net-(IC6-FB)") (class "Default")
      (node (ref "IC6") (pin "3") (pinfunction "FB_3") (pintype "input"))
      (node (ref "R211") (pin "2") (pinfunction "2_2") (pintype "passive"))
      (node (ref "R212") (pin "2") (pinfunction "2_2") (pintype "passive"))
    )
    (net (code "61") (name "Net-(IC6-SW)") (class "Default")
      (node (ref "D211") (pin "C") (pinfunction "C_C") (pintype "passive"))
      (node (ref "IC6") (pin "1") (pinfunction "SW_1") (pintype "output"))
      (node (ref "L211") (pin "2") (pinfunction "2_2") (pintype "passive"))
    )
    (net (code "62") (name "Net-(IC11-Pad14)") (class "Default")
      (node (ref "IC11") (pin "14") (pinfunction "14_14") (pintype "power_in"))
      (node (ref "LFP111") (pin "1") (pinfunction "1_1") (pintype "passive"))
    )
    (net (code "63") (name "VCC") (class "Default")
      (node (ref "C1") (pin "+") (pinfunction "+_+") (pintype "passive"))
      (node (ref "C2") (pin "1") (pinfunction "1_1") (pintype "passive"))
      (node (ref "C211") (pin "+") (pinfunction "+_+") (pintype "passive"))
      (node (ref "C911") (pin "1") (pinfunction "1_1") (pintype "passive"))
      (node (ref "C931") (pin "1") (pinfunction "1_1") (pintype "passive"))
      (node (ref "C951") (pin "1") (pinfunction "1_1") (pintype "passive"))
      (node (ref "CON5") (pin "7") (pinfunction "7_7") (pintype "passive"))
      (node (ref "CON6") (pin "3") (pinfunction "3_3") (pintype "passive"))
      (node (ref "IC1") (pin "7") (pinfunction "VCC_7") (pintype "bidirectional"))
      (node (ref "IC3") (pin "10") (pinfunction "B_10") (pintype "input"))
      (node (ref "IC3") (pin "11") (pinfunction "R_11") (pintype "input"))
      (node (ref "IC3") (pin "16") (pinfunction "VCC_16") (pintype "power_in"))
      (node (ref "IC3") (pin "2") (pinfunction "B_2") (pintype "input"))
      (node (ref "IC3") (pin "3") (pinfunction "R_3") (pintype "input"))
      (node (ref "IC5") (pin "5") (pinfunction "VS+_5") (pintype "power_in"))
      (node (ref "IC6") (pin "5") (pinfunction "VIN_5") (pintype "power_in"))
      (node (ref "JP2") (pin "2") (pinfunction "2_2") (pintype "passive"))
      (node (ref "L31") (pin "2") (pinfunction "2_2") (pintype "passive"))
      (node (ref "R213") (pin "1") (pinfunction "1_1") (pintype "passive"))
      (node (ref "R31") (pin "3") (pinfunction "E_3") (pintype "passive"))
      (node (ref "R41") (pin "1") (pinfunction "1_1") (pintype "passive"))
      (node (ref "R71") (pin "2") (pinfunction "2_2") (pintype "passive"))
      (node (ref "R72") (pin "1") (pinfunction "A_1") (pintype "passive"))
      (node (ref "R81") (pin "2") (pinfunction "2_2") (pintype "passive"))
      (node (ref "RPOLY1") (pin "2") (pinfunction "2_2") (pintype "passive"))
    )
    (net (code "64") (name "unconnected-(CON5-Pad8)") (class "Default")
      (node (ref "CON5") (pin "8") (pinfunction "8_8") (pintype "passive"))
    )
    (net (code "65") (name "unconnected-(IC1-PB7(XTAL2{slash}TOSC2)-Pad10)") (class "Default")
      (node (ref "IC1") (pin "10") (pinfunction "PB7(XTAL2/TOSC2)_10") (pintype "bidirectional"))
    )
    (net (code "66") (name "unconnected-(IC2-IOA1-Pad41)") (class "Default")
      (node (ref "IC2") (pin "41") (pinfunction "IOA1_41") (pintype "bidirectional"))
    )
    (net (code "67") (name "unconnected-(IC2-IOA2-Pad42)") (class "Default")
      (node (ref "IC2") (pin "42") (pinfunction "IOA2_42") (pintype "bidirectional"))
    )
    (net (code "68") (name "unconnected-(IC2-IOA3-Pad43)") (class "Default")
      (node (ref "IC2") (pin "43") (pinfunction "IOA3_43") (pintype "bidirectional"))
    )
    (net (code "69") (name "unconnected-(IC2-IOA5-Pad2)") (class "Default")
      (node (ref "IC2") (pin "2") (pinfunction "IOA5_2") (pintype "bidirectional"))
    )
    (net (code "70") (name "unconnected-(IC2-IOA6-Pad3)") (class "Default")
      (node (ref "IC2") (pin "3") (pinfunction "IOA6_3") (pintype "bidirectional"))
    )
    (net (code "71") (name "unconnected-(IC2-IOA13-Pad14)") (class "Default")
      (node (ref "IC2") (pin "14") (pinfunction "IOA13_14") (pintype "bidirectional"))
    )
    (net (code "72") (name "unconnected-(IC2-IOA14-Pad15)") (class "Default")
      (node (ref "IC2") (pin "15") (pinfunction "IOA14_15") (pintype "bidirectional"))
    )
    (net (code "73") (name "unconnected-(IC2-IOB0-Pad18)") (class "Default")
      (node (ref "IC2") (pin "18") (pinfunction "IOB0_18") (pintype "bidirectional"))
    )
    (net (code "74") (name "unconnected-(IC2-IOB1-Pad19)") (class "Default")
      (node (ref "IC2") (pin "19") (pinfunction "IOB1_19") (pintype "bidirectional"))
    )
    (net (code "75") (name "unconnected-(IC2-IOB2-Pad20)") (class "Default")
      (node (ref "IC2") (pin "20") (pinfunction "IOB2_20") (pintype "bidirectional"))
    )
    (net (code "76") (name "unconnected-(IC2-IOB3-Pad21)") (class "Default")
      (node (ref "IC2") (pin "21") (pinfunction "IOB3_21") (pintype "bidirectional"))
    )
    (net (code "77") (name "unconnected-(IC2-IOB4-Pad22)") (class "Default")
      (node (ref "IC2") (pin "22") (pinfunction "IOB4_22") (pintype "bidirectional"))
    )
    (net (code "78") (name "unconnected-(IC2-IOB5-Pad24)") (class "Default")
      (node (ref "IC2") (pin "24") (pinfunction "IOB5_24") (pintype "bidirectional"))
    )
    (net (code "79") (name "unconnected-(IC2-IOB6-Pad25)") (class "Default")
      (node (ref "IC2") (pin "25") (pinfunction "IOB6_25") (pintype "bidirectional"))
    )
    (net (code "80") (name "unconnected-(IC2-IOB7-Pad26)") (class "Default")
      (node (ref "IC2") (pin "26") (pinfunction "IOB7_26") (pintype "bidirectional"))
    )
    (net (code "81") (name "unconnected-(IC2-IOB8-Pad29)") (class "Default")
      (node (ref "IC2") (pin "29") (pinfunction "IOB8_29") (pintype "bidirectional"))
    )
    (net (code "82") (name "unconnected-(IC2-IOB9-Pad30)") (class "Default")
      (node (ref "IC2") (pin "30") (pinfunction "IOB9_30") (pintype "bidirectional"))
    )
    (net (code "83") (name "unconnected-(IC3A-~{Q}-Pad4)") (class "Default")
      (node (ref "IC3") (pin "4") (pinfunction "~{Q}_4") (pintype "output"))
    )
    (net (code "84") (name "unconnected-(IC3B-~{Q}-Pad12)") (class "Default")
      (node (ref "IC3") (pin "12") (pinfunction "~{Q}_12") (pintype "output"))
    )
    (net (code "85") (name "unconnected-(IC11-Pad5)") (class "Default")
      (node (ref "IC11") (pin "5") (pinfunction "5_5") (pintype "no_connect"))
    )
    (net (code "86") (name "unconnected-(IC11-Pad7)") (class "Default")
      (node (ref "IC11") (pin "7") (pinfunction "7_7") (pintype "bidirectional"))
    )
    (net (code "87") (name "unconnected-(IC11-Pad9)") (class "Default")
      (node (ref "IC11") (pin "9") (pinfunction "9_9") (pintype "no_connect"))
    )
    (net (code "88") (name "unconnected-(IC11-Pad13)") (class "Default")
      (node (ref "IC11") (pin "13") (pinfunction "13_13") (pintype "no_connect"))
    )
    (net (code "89") (name "unconnected-(IC11-Pad15)") (class "Default")
      (node (ref "IC11") (pin "15") (pinfunction "15_15") (pintype "no_connect"))
    )
    (net (code "90") (name "unconnected-(IC11-Pad16)") (class "Default")
      (node (ref "IC11") (pin "16") (pinfunction "16_16") (pintype "no_connect"))
    )
    (net (code "91") (name "unconnected-(IC11-Pad17)") (class "Default")
      (node (ref "IC11") (pin "17") (pinfunction "17_17") (pintype "no_connect"))
    )
    (net (code "92") (name "unconnected-(IC11-Pad18)") (class "Default")
      (node (ref "IC11") (pin "18") (pinfunction "18_18") (pintype "no_connect"))
    )
    (net (code "93") (name "unconnected-(R72-E-Pad3)") (class "Default")
      (node (ref "R72") (pin "3") (pinfunction "E_3") (pintype "passive"))
    )
  )
)
